# Rotary_Encoder_-_basic.net
KiCad netlist of a schematic drawn in EAGLE
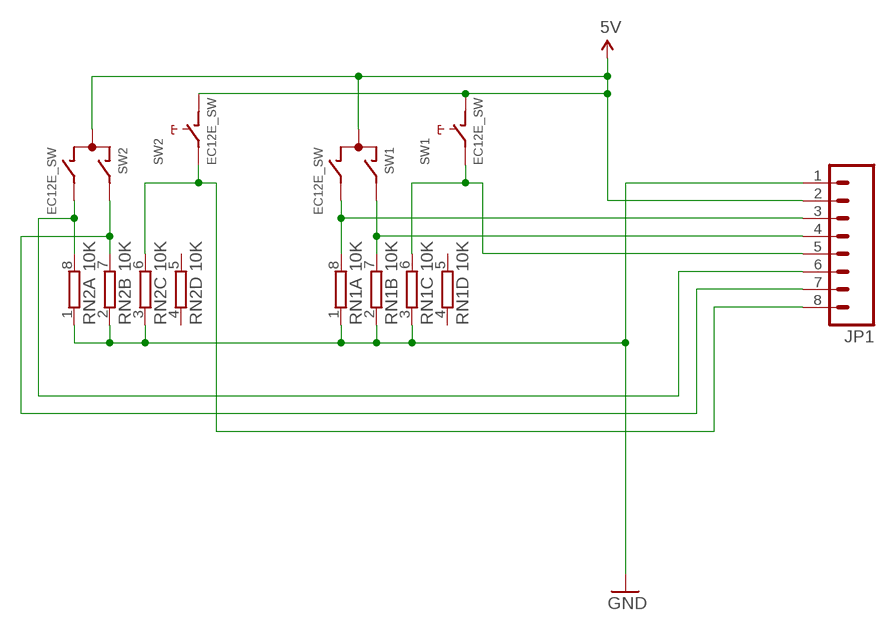
[diagram p0: schematic, sheet 1]

(export (version "E")
  (design (tool "Eeschema 10.0.6"))
  (components
    (comp (ref "JP1")
      (value "M08LOCK")
      (footprint "eagle-import:1X08_LOCK")
      (libsource (lib "eagle-import") (part "M08LOCK"))
    )
    (comp (ref "RN1")
      (value "10K")
      (footprint "eagle-import:CAY16_HAND")
      (libsource (lib "eagle-import") (part "4R-NCAY16"))
    )
    (comp (ref "RN2")
      (value "10K")
      (footprint "eagle-import:CAY16_HAND")
      (libsource (lib "eagle-import") (part "4R-NCAY16"))
    )
    (comp (ref "SW1")
      (value "EC12E_SW")
      (footprint "eagle-import:ALPS_EC12E_SW")
      (fields (field (name "MPN") "EC12E2424407"))
      (libsource (lib "eagle-import") (part "EC12E_SW"))
    )
    (comp (ref "SW2")
      (value "EC12E_SW")
      (footprint "eagle-import:ALPS_EC12E_SW")
      (fields (field (name "MPN") "EC12E2424407"))
      (libsource (lib "eagle-import") (part "EC12E_SW"))
    )
  )
  (nets
    (net (code "1") (name "5V") (class "Default")
      (node (ref "JP1") (pin "2") (pinfunction "2_2") (pintype "passive"))
      (node (ref "SW1") (pin "C") (pinfunction "C_C") (pintype "passive"))
      (node (ref "SW1") (pin "D") (pinfunction "1_D") (pintype "passive"))
      (node (ref "SW2") (pin "C") (pinfunction "C_C") (pintype "passive"))
      (node (ref "SW2") (pin "D") (pinfunction "1_D") (pintype "passive"))
    )
    (net (code "2") (name "GND") (class "Default")
      (node (ref "JP1") (pin "1") (pinfunction "1_1") (pintype "passive"))
      (node (ref "RN1") (pin "1") (pinfunction "1_1") (pintype "passive"))
      (node (ref "RN1") (pin "2") (pinfunction "1_2") (pintype "passive"))
      (node (ref "RN1") (pin "3") (pinfunction "1_3") (pintype "passive"))
      (node (ref "RN2") (pin "1") (pinfunction "1_1") (pintype "passive"))
      (node (ref "RN2") (pin "2") (pinfunction "1_2") (pintype "passive"))
      (node (ref "RN2") (pin "3") (pinfunction "1_3") (pintype "passive"))
    )
    (net (code "3") (name "Net-(RN1A-2)") (class "Default")
      (node (ref "JP1") (pin "3") (pinfunction "3_3") (pintype "passive"))
      (node (ref "RN1") (pin "8") (pinfunction "2_8") (pintype "passive"))
      (node (ref "SW1") (pin "B") (pinfunction "B_B") (pintype "passive"))
    )
    (net (code "4") (name "Net-(RN1B-2)") (class "Default")
      (node (ref "JP1") (pin "4") (pinfunction "4_4") (pintype "passive"))
      (node (ref "RN1") (pin "7") (pinfunction "2_7") (pintype "passive"))
      (node (ref "SW1") (pin "A") (pinfunction "A_A") (pintype "passive"))
    )
    (net (code "5") (name "Net-(RN1C-2)") (class "Default")
      (node (ref "JP1") (pin "5") (pinfunction "5_5") (pintype "passive"))
      (node (ref "RN1") (pin "6") (pinfunction "2_6") (pintype "passive"))
      (node (ref "SW1") (pin "E") (pinfunction "2_E") (pintype "passive"))
    )
    (net (code "6") (name "Net-(RN2A-2)") (class "Default")
      (node (ref "JP1") (pin "6") (pinfunction "6_6") (pintype "passive"))
      (node (ref "RN2") (pin "8") (pinfunction "2_8") (pintype "passive"))
      (node (ref "SW2") (pin "B") (pinfunction "B_B") (pintype "passive"))
    )
    (net (code "7") (name "Net-(RN2B-2)") (class "Default")
      (node (ref "JP1") (pin "7") (pinfunction "7_7") (pintype "passive"))
      (node (ref "RN2") (pin "7") (pinfunction "2_7") (pintype "passive"))
      (node (ref "SW2") (pin "A") (pinfunction "A_A") (pintype "passive"))
    )
    (net (code "8") (name "Net-(RN2C-2)") (class "Default")
      (node (ref "JP1") (pin "8") (pinfunction "8_8") (pintype "passive"))
      (node (ref "RN2") (pin "6") (pinfunction "2_6") (pintype "passive"))
      (node (ref "SW2") (pin "E") (pinfunction "2_E") (pintype "passive"))
    )
    (net (code "9") (name "unconnected-(RN1D-1-Pad4)") (class "Default")
      (node (ref "RN1") (pin "4") (pinfunction "1_4") (pintype "passive"))
    )
    (net (code "10") (name "unconnected-(RN1D-2-Pad5)") (class "Default")
      (node (ref "RN1") (pin "5") (pinfunction "2_5") (pintype "passive"))
    )
    (net (code "11") (name "unconnected-(RN2D-1-Pad4)") (class "Default")
      (node (ref "RN2") (pin "4") (pinfunction "1_4") (pintype "passive"))
    )
    (net (code "12") (name "unconnected-(RN2D-2-Pad5)") (class "Default")
      (node (ref "RN2") (pin "5") (pinfunction "2_5") (pintype "passive"))
    )
  )
)
